# ESP32_WITH_USB_C.net
KiCad netlist of a schematic drawn in Altium Designer
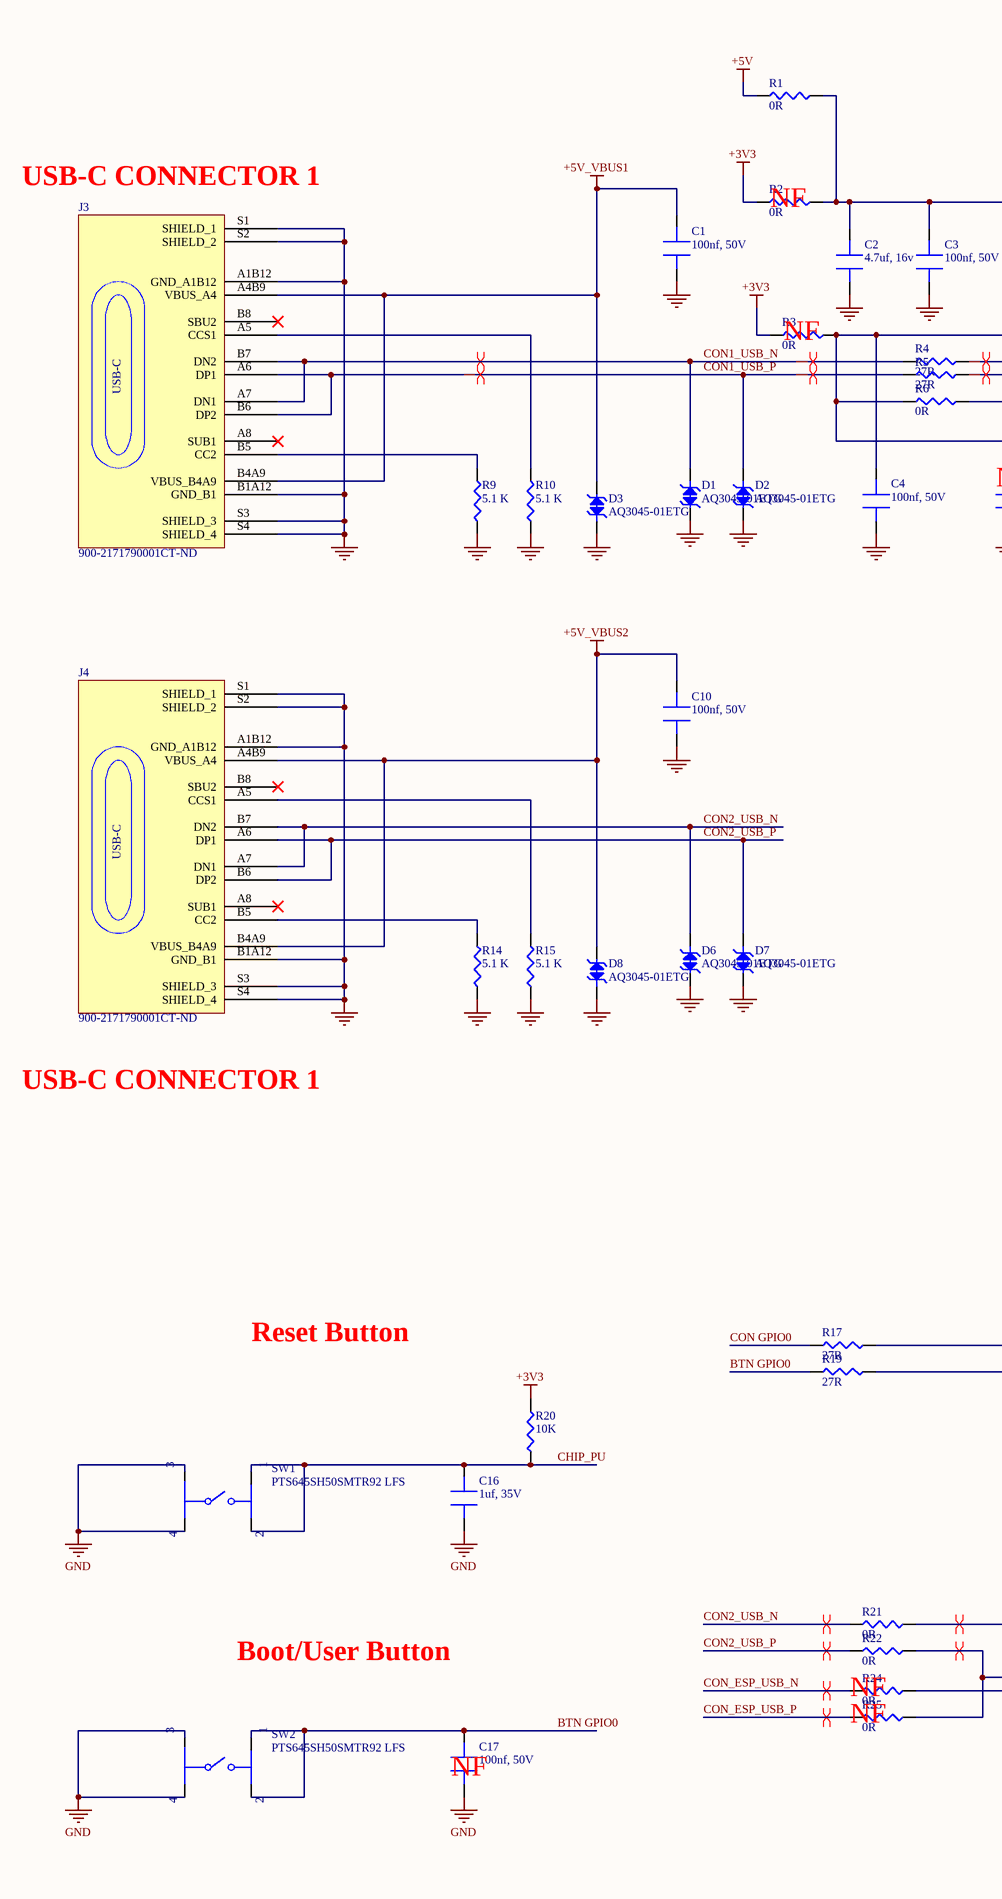
[diagram p0: ESP32 WITH USB C.SchDoc, left]
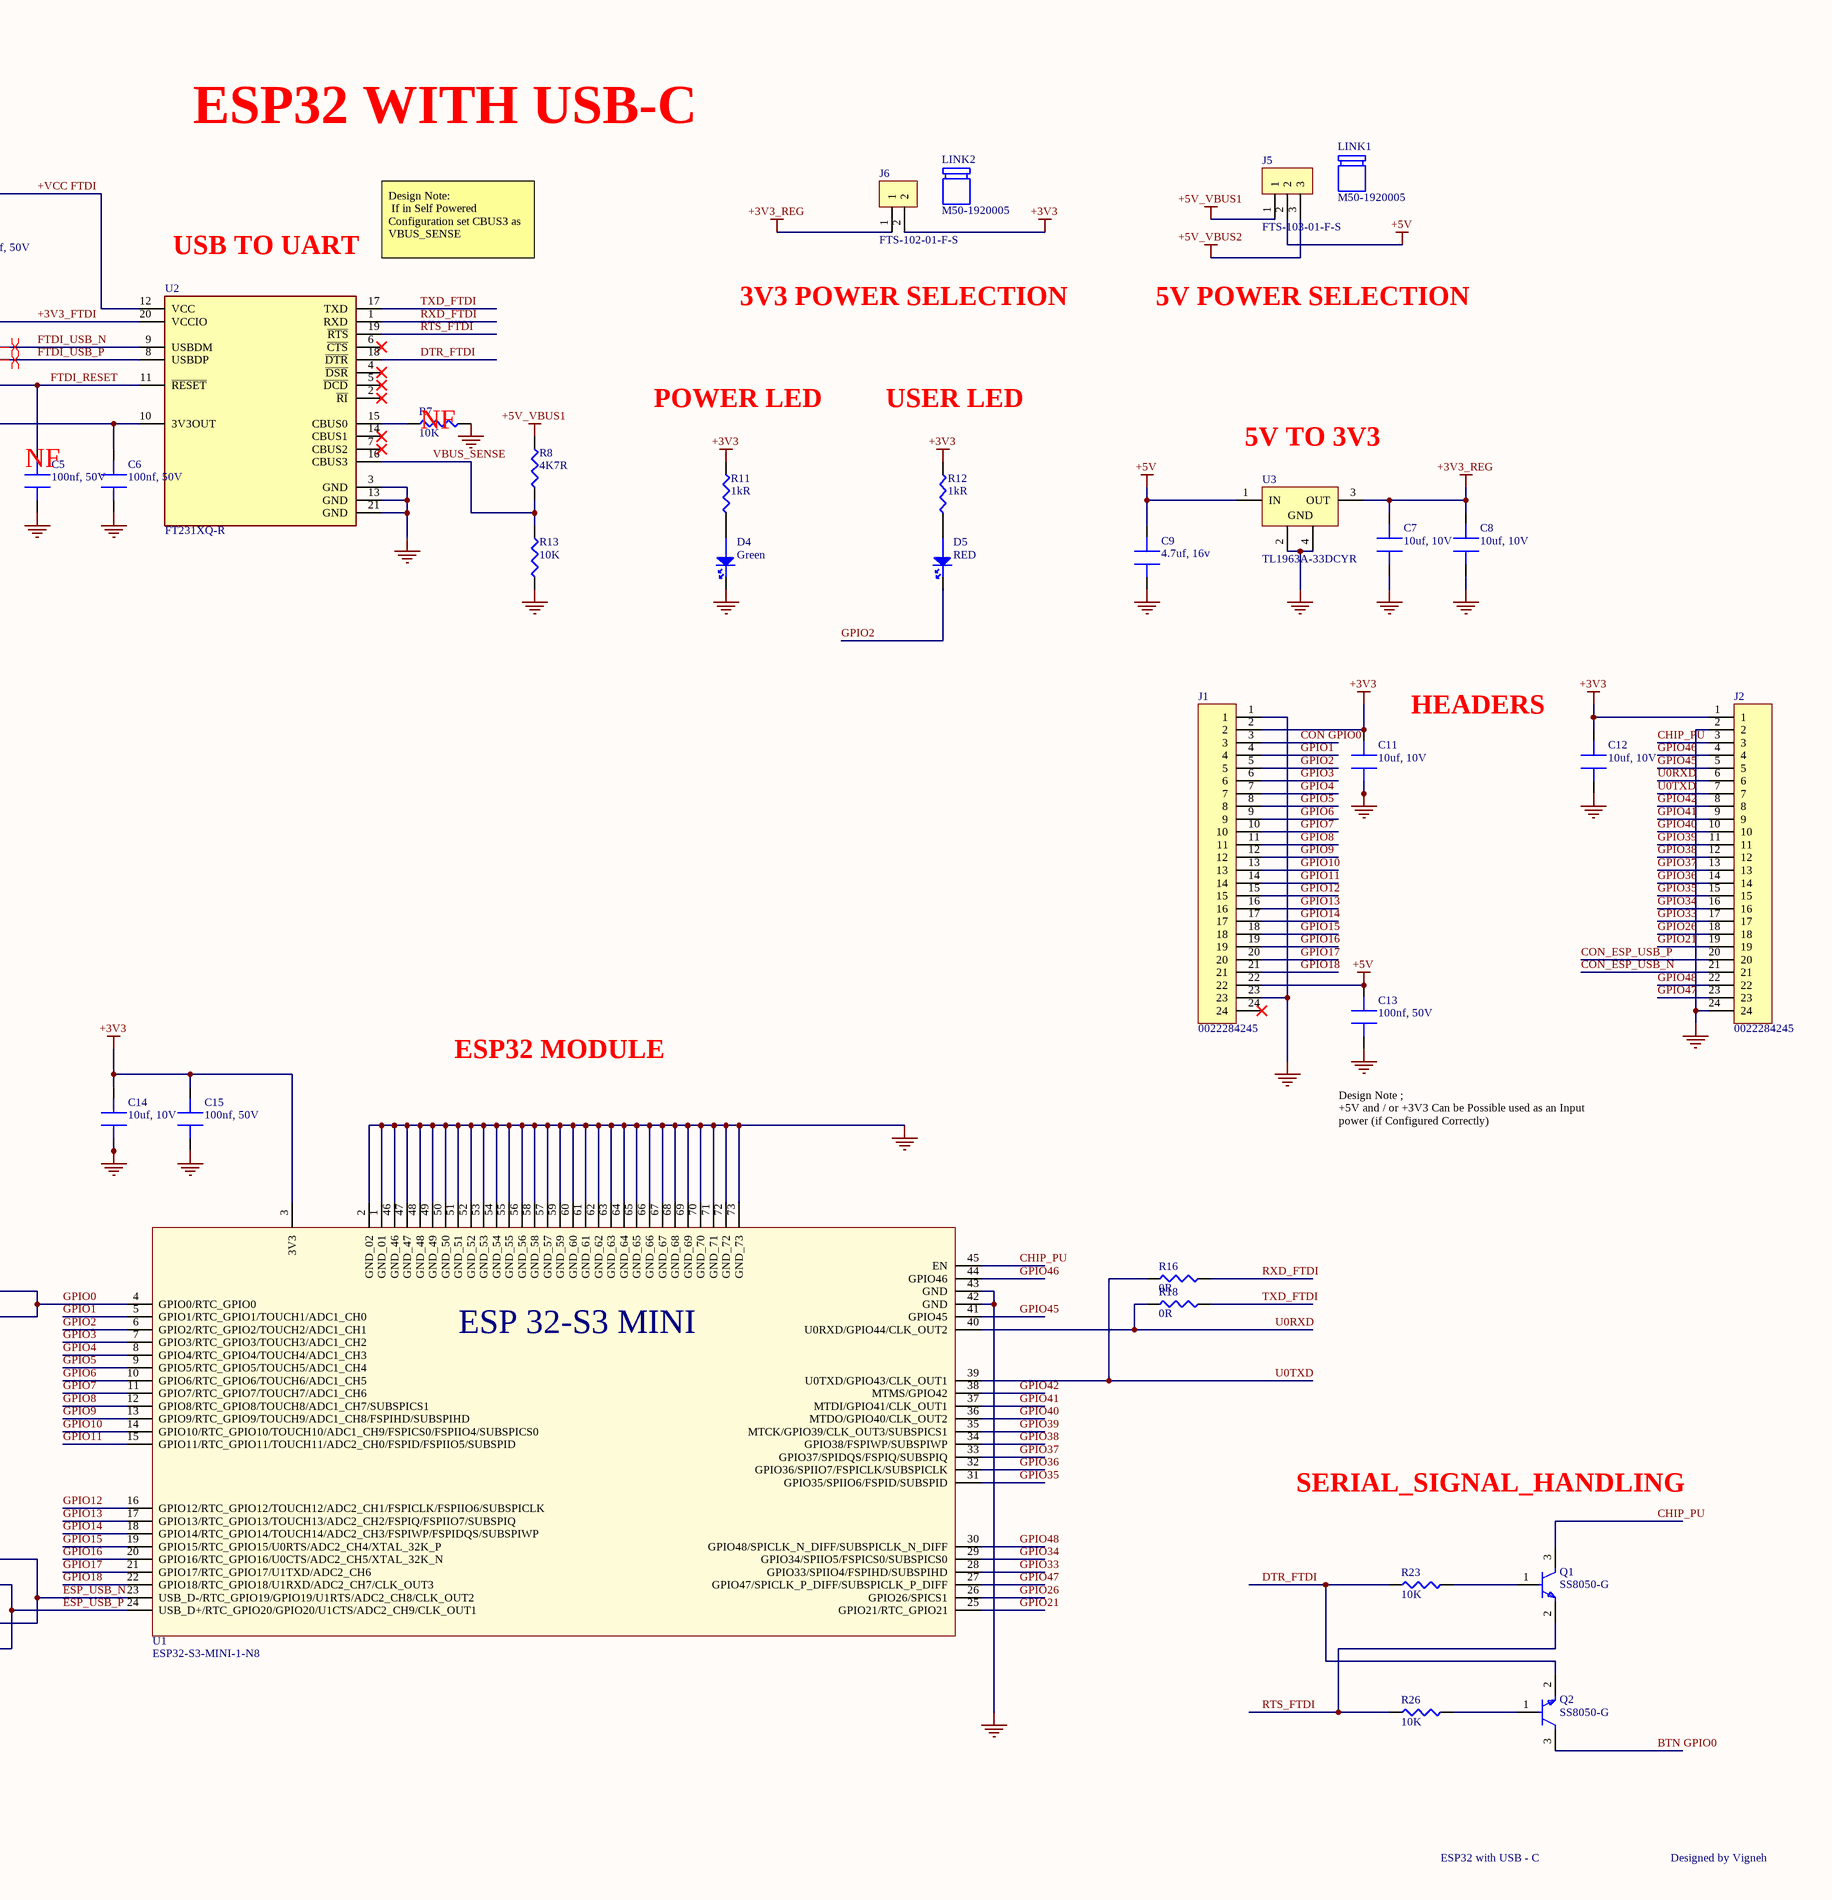
[diagram p1: ESP32 WITH USB C.SchDoc, right]

(export (version "E")
  (design (tool "Eeschema 10.0.6"))
  (components
    (comp (ref "C1")
      (value "100nf, 50V")
      (footprint "CAPC1005X70N")
      (description "CAP CER 0.1UF 50V X7R 0402")
      (fields
        (field (name "MANUFACTURER") "Samsung")
        (field (name "MANUFACTURER PART NUMBER") "CL05B104KB54PNC")
      )
      (libsource (lib "Schlib") (part "CL05B104KB54PNC"))
    )
    (comp (ref "C2")
      (value "4.7uf, 16v")
      (footprint "CAPC1005X70N")
      (description "4.7 µF ±20% 16V Ceramic Capacitor X5R 0402 (1005 Metric)")
      (fields
        (field (name "MANUFACTURER") "Samsung")
        (field (name "MANUFACTURER PART NUMBER") "CL05A475MO5NUNC")
      )
      (libsource (lib "Schlib") (part "CL05A475MO5NUNC"))
    )
    (comp (ref "C3")
      (value "100nf, 50V")
      (footprint "CAPC1005X70N")
      (description "CAP CER 0.1UF 50V X7R 0402")
      (fields
        (field (name "MANUFACTURER") "Samsung")
        (field (name "MANUFACTURER PART NUMBER") "CL05B104KB54PNC")
      )
      (libsource (lib "Schlib") (part "CL05B104KB54PNC"))
    )
    (comp (ref "C4")
      (value "100nf, 50V")
      (footprint "CAPC1005X70N")
      (description "CAP CER 0.1UF 50V X7R 0402")
      (fields
        (field (name "MANUFACTURER") "Samsung")
        (field (name "MANUFACTURER PART NUMBER") "CL05B104KB54PNC")
      )
      (libsource (lib "Schlib") (part "CL05B104KB54PNC"))
    )
    (comp (ref "C5")
      (value "100nf, 50V")
      (footprint "CAPC1005X70N")
      (description "CAP CER 0.1UF 50V X7R 0402")
      (fields
        (field (name "MANUFACTURER") "Samsung")
        (field (name "MANUFACTURER PART NUMBER") "CL05B104KB54PNC")
      )
      (libsource (lib "Schlib") (part "CL05B104KB54PNC"))
    )
    (comp (ref "C6")
      (value "100nf, 50V")
      (footprint "CAPC1005X70N")
      (description "CAP CER 0.1UF 50V X7R 0402")
      (fields
        (field (name "MANUFACTURER") "Samsung")
        (field (name "MANUFACTURER PART NUMBER") "CL05B104KB54PNC")
      )
      (libsource (lib "Schlib") (part "CL05B104KB54PNC"))
    )
    (comp (ref "C7")
      (value "10uf, 10V")
      (footprint "CAPC1005X70N")
      (description "CAP CER 10UF 10V X5R 0402")
      (fields
        (field (name "MANUFACTURER") "Samsung")
        (field (name "MANUFACTURER PART NUMBER") "CL05A106MP8NUB8")
      )
      (libsource (lib "Schlib") (part "CL05A106MP8NUB8"))
    )
    (comp (ref "C8")
      (value "10uf, 10V")
      (footprint "CAPC1005X70N")
      (description "CAP CER 10UF 10V X5R 0402")
      (fields
        (field (name "MANUFACTURER") "Samsung")
        (field (name "MANUFACTURER PART NUMBER") "CL05A106MP8NUB8")
      )
      (libsource (lib "Schlib") (part "CL05A106MP8NUB8"))
    )
    (comp (ref "C9")
      (value "4.7uf, 16v")
      (footprint "CAPC1005X70N")
      (description "4.7 µF ±20% 16V Ceramic Capacitor X5R 0402 (1005 Metric)")
      (fields
        (field (name "MANUFACTURER") "Samsung")
        (field (name "MANUFACTURER PART NUMBER") "CL05A475MO5NUNC")
      )
      (libsource (lib "Schlib") (part "CL05A475MO5NUNC"))
    )
    (comp (ref "C10")
      (value "100nf, 50V")
      (footprint "CAPC1005X70N")
      (description "CAP CER 0.1UF 50V X7R 0402")
      (fields
        (field (name "MANUFACTURER") "Samsung")
        (field (name "MANUFACTURER PART NUMBER") "CL05B104KB54PNC")
      )
      (libsource (lib "Schlib") (part "CL05B104KB54PNC"))
    )
    (comp (ref "C11")
      (value "10uf, 10V")
      (footprint "CAPC1005X70N")
      (description "CAP CER 10UF 10V X5R 0402")
      (fields
        (field (name "MANUFACTURER") "Samsung")
        (field (name "MANUFACTURER PART NUMBER") "CL05A106MP8NUB8")
      )
      (libsource (lib "Schlib") (part "CL05A106MP8NUB8"))
    )
    (comp (ref "C12")
      (value "10uf, 10V")
      (footprint "CAPC1005X70N")
      (description "CAP CER 10UF 10V X5R 0402")
      (fields
        (field (name "MANUFACTURER") "Samsung")
        (field (name "MANUFACTURER PART NUMBER") "CL05A106MP8NUB8")
      )
      (libsource (lib "Schlib") (part "CL05A106MP8NUB8"))
    )
    (comp (ref "C13")
      (value "100nf, 50V")
      (footprint "CAPC1005X70N")
      (description "CAP CER 0.1UF 50V X7R 0402")
      (fields
        (field (name "MANUFACTURER") "Samsung")
        (field (name "MANUFACTURER PART NUMBER") "CL05B104KB54PNC")
      )
      (libsource (lib "Schlib") (part "CL05B104KB54PNC"))
    )
    (comp (ref "C14")
      (value "10uf, 10V")
      (footprint "CAPC1005X70N")
      (description "CAP CER 10UF 10V X5R 0402")
      (fields
        (field (name "MANUFACTURER") "Samsung")
        (field (name "MANUFACTURER PART NUMBER") "CL05A106MP8NUB8")
      )
      (libsource (lib "Schlib") (part "CL05A106MP8NUB8"))
    )
    (comp (ref "C15")
      (value "100nf, 50V")
      (footprint "CAPC1005X70N")
      (description "CAP CER 0.1UF 50V X7R 0402")
      (fields
        (field (name "MANUFACTURER") "Samsung")
        (field (name "MANUFACTURER PART NUMBER") "CL05B104KB54PNC")
      )
      (libsource (lib "Schlib") (part "CL05B104KB54PNC"))
    )
    (comp (ref "C16")
      (value "1uf, 35V")
      (footprint "CAPC1005X70N")
      (description "CAP CER 1UF 35V X5R 0402")
      (fields
        (field (name "MANUFACTURER") "Samsung")
        (field (name "MANUFACTURER PART NUMBER") "CL05A105KL5NRNC")
      )
      (libsource (lib "Schlib") (part "CL05A105KL5NRNC"))
    )
    (comp (ref "C17")
      (value "100nf, 50V")
      (footprint "CAPC1005X70N")
      (description "CAP CER 0.1UF 50V X7R 0402")
      (fields
        (field (name "MANUFACTURER") "Samsung")
        (field (name "MANUFACTURER PART NUMBER") "CL05B104KB54PNC")
      )
      (libsource (lib "Schlib") (part "CL05B104KB54PNC"))
    )
    (comp (ref "D1")
      (value "AQ3045-01ETG")
      (footprint "SOD882")
      (description "TVS DIODE 5.3VWM 12VC SOD882")
      (fields (field (name "MANUFACTURER") "Littelfuse") (field (name "LCSC PART NO") "C3710326"))
      (libsource (lib "Schlib") (part "AQ3045-01ETG"))
    )
    (comp (ref "D2")
      (value "AQ3045-01ETG")
      (footprint "SOD882")
      (description "TVS DIODE 5.3VWM 12VC SOD882")
      (fields (field (name "MANUFACTURER") "Littelfuse") (field (name "LCSC PART NO") "C3710326"))
      (libsource (lib "Schlib") (part "AQ3045-01ETG"))
    )
    (comp (ref "D3")
      (value "AQ3045-01ETG")
      (footprint "SOD882")
      (description "TVS DIODE 5.3VWM 12VC SOD882")
      (fields (field (name "MANUFACTURER") "Littelfuse") (field (name "LCSC PART NO") "C3710326"))
      (libsource (lib "Schlib") (part "AQ3045-01ETG"))
    )
    (comp (ref "D4")
      (value "Green")
      (footprint "LED0402G")
      (description "LED YLW-GRN 0402 SMD")
      (fields
        (field (name "MANUFACTURER") "Vishay")
        (field (name "MANUFACTURER PART NUMBER") "VLMG1500-GS08")
      )
      (libsource (lib "Schlib") (part "VLMG1500-GS08"))
    )
    (comp (ref "D5")
      (value "RED")
      (footprint "LED0402R")
      (description "LED RED 0402 SMD")
      (fields
        (field (name "MANUFACTURER") "Vishay")
        (field (name "MANUFACTURER PART NUMBER") "VLMS1500-GS08")
      )
      (libsource (lib "Schlib") (part "VLMS1500-GS08"))
    )
    (comp (ref "D6")
      (value "AQ3045-01ETG")
      (footprint "SOD882")
      (description "TVS DIODE 5.3VWM 12VC SOD882")
      (fields (field (name "MANUFACTURER") "Littelfuse") (field (name "LCSC PART NO") "C3710326"))
      (libsource (lib "Schlib") (part "AQ3045-01ETG"))
    )
    (comp (ref "D7")
      (value "AQ3045-01ETG")
      (footprint "SOD882")
      (description "TVS DIODE 5.3VWM 12VC SOD882")
      (fields (field (name "MANUFACTURER") "Littelfuse") (field (name "LCSC PART NO") "C3710326"))
      (libsource (lib "Schlib") (part "AQ3045-01ETG"))
    )
    (comp (ref "D8")
      (value "AQ3045-01ETG")
      (footprint "SOD882")
      (description "TVS DIODE 5.3VWM 12VC SOD882")
      (fields (field (name "MANUFACTURER") "Littelfuse") (field (name "LCSC PART NO") "C3710326"))
      (libsource (lib "Schlib") (part "AQ3045-01ETG"))
    )
    (comp (ref "J1")
      (value "0022284245")
      (footprint "HDR_1x24_2.5MM")
      (description "CONN HEADER VERT 24POS 2.54MM")
      (fields (field (name "MANUFACTURER") "Molex") (field (name "MANUFACTURER PART NUMBER") "22-28-4245"))
      (libsource (lib "Schlib") (part "0022284245"))
    )
    (comp (ref "J2")
      (value "0022284245")
      (footprint "HDR_1x24_2.5MM")
      (description "CONN HEADER VERT 24POS 2.54MM")
      (fields (field (name "MANUFACTURER") "Molex") (field (name "MANUFACTURER PART NUMBER") "22-28-4245"))
      (libsource (lib "") (part "0022284245_1"))
    )
    (comp (ref "J3")
      (value "900-2171790001CT-ND")
      (footprint "FP-2171790001-MFG")
      (description "CONN RCP USB2.0 TYP C 24P SMD RA")
      (fields (field (name "MANUFACTURER") "Molex") (field (name "MANUFACTURER PART NUMBER") "217179-0001"))
      (libsource (lib "Schlib") (part "2171790001"))
    )
    (comp (ref "J4")
      (value "900-2171790001CT-ND")
      (footprint "FP-2171790001-MFG")
      (description "CONN RCP USB2.0 TYP C 24P SMD RA")
      (fields (field (name "MANUFACTURER") "Molex") (field (name "MANUFACTURER PART NUMBER") "217179-0001"))
      (libsource (lib "Schlib") (part "2171790001"))
    )
    (comp (ref "J5")
      (value "FTS-103-01-F-S")
      (footprint "HDR_1x3_1.27MM")
      (description "CONN HEADER VERT 3POS 1.27MM")
      (fields (field (name "MANUFACTURER") "Samtec") (field (name "LCSC PART NUMBER") "C3333578"))
      (libsource (lib "Schlib") (part "FTS-103-01-F-S"))
    )
    (comp (ref "J6")
      (value "FTS-102-01-F-S")
      (footprint "HDR_1x2_1.27MM")
      (description "CONN HEADER VERT 2POS 1.27MM")
      (fields (field (name "MANUFACTURER") "Samtec") (field (name "LCSC PART NUMBER") "C6045317"))
      (libsource (lib "Schlib") (part "FTS-102-01-F-S"))
    )
    (comp (ref "LINK1")
      (value "M50-1920005")
      (description "CONN SHUNT 1.27MM RED")
      (fields (field (name "MANUFACTURER") "Harwin") (field (name "LCSC PART NUMBER") "C6985646"))
      (libsource (lib "Schlib") (part "M50-1920005"))
    )
    (comp (ref "LINK2")
      (value "M50-1920005")
      (description "CONN SHUNT 1.27MM RED")
      (fields (field (name "MANUFACTURER") "Harwin") (field (name "LCSC PART NUMBER") "C6985646"))
      (libsource (lib "Schlib") (part "M50-1920005"))
    )
    (comp (ref "Q1")
      (value "SS8050-G")
      (footprint "FP-SS8050-G-IPC_B")
      (description "TRANS NPN 25V 1.5A SOT-23-3")
      (fields (field (name "MANUFACTURER") "Comchip") (field (name "LCSC PART NUMBER") "C164886"))
      (libsource (lib "Schlib") (part "SS8050-G"))
    )
    (comp (ref "Q2")
      (value "SS8050-G")
      (footprint "FP-SS8050-G-IPC_B")
      (description "TRANS NPN 25V 1.5A SOT-23-3")
      (fields (field (name "MANUFACTURER") "Comchip") (field (name "LCSC PART NUMBER") "C164886"))
      (libsource (lib "Schlib") (part "SS8050-G"))
    )
    (comp (ref "R1")
      (value "0R")
      (footprint "RESC1005X40N")
      (description "RES 0 OHM JUMPER 1/16W 0402")
      (fields
        (field (name "MANUFACTURER") "Yageo")
        (field (name "MANUFACTURER PART NUMBER") "RC0402JR-070RL")
      )
      (libsource (lib "Schlib") (part "RC0402JR-070RL"))
    )
    (comp (ref "R2")
      (value "0R")
      (footprint "RESC1005X40N")
      (description "RES 0 OHM JUMPER 1/16W 0402")
      (fields
        (field (name "MANUFACTURER") "Yageo")
        (field (name "MANUFACTURER PART NUMBER") "RC0402JR-070RL")
      )
      (libsource (lib "Schlib") (part "RC0402JR-070RL"))
    )
    (comp (ref "R3")
      (value "0R")
      (footprint "RESC1005X40N")
      (description "RES 0 OHM JUMPER 1/16W 0402")
      (fields
        (field (name "MANUFACTURER") "Yageo")
        (field (name "MANUFACTURER PART NUMBER") "RC0402JR-070RL")
      )
      (libsource (lib "Schlib") (part "RC0402JR-070RL"))
    )
    (comp (ref "R4")
      (value "27R")
      (footprint "RESC1005X40N")
      (description "RES 27 OHM 1% 1/16W 0402")
      (fields
        (field (name "MANUFACTURER") "Yageo")
        (field (name "MANUFACTURER PART NUMBER") "RC0402FR-0727RL")
      )
      (libsource (lib "Schlib") (part "RC0402FR-0727RL"))
    )
    (comp (ref "R5")
      (value "27R")
      (footprint "RESC1005X40N")
      (description "RES 27 OHM 1% 1/16W 0402")
      (fields
        (field (name "MANUFACTURER") "Yageo")
        (field (name "MANUFACTURER PART NUMBER") "RC0402FR-0727RL")
      )
      (libsource (lib "Schlib") (part "RC0402FR-0727RL"))
    )
    (comp (ref "R6")
      (value "0R")
      (footprint "RESC1005X40N")
      (description "RES 0 OHM JUMPER 1/16W 0402")
      (fields
        (field (name "MANUFACTURER") "Yageo")
        (field (name "MANUFACTURER PART NUMBER") "RC0402JR-070RL")
      )
      (libsource (lib "Schlib") (part "RC0402JR-070RL"))
    )
    (comp (ref "R7")
      (value "10K")
      (footprint "RESC1005X40N")
      (description "RES SMD 10K OHM 1% 1/16W 0402")
      (fields
        (field (name "MANUFACTURER") "Yageo")
        (field (name "MANUFACTURER PART NUMBER") "AC0402FR-0710KL")
      )
      (libsource (lib "Schlib") (part "AC0402FR-0710KL"))
    )
    (comp (ref "R8")
      (value "4K7R")
      (footprint "RESC1005X40N")
      (description "RES 4.7K OHM 1% 1/16W 0402")
      (fields
        (field (name "MANUFACTURER") "Yageo")
        (field (name "MANUFACTURER PART NUMBER") "RC0402FR-074K7L")
      )
      (libsource (lib "Schlib") (part "RC0402FR-074K7L"))
    )
    (comp (ref "R9")
      (value "5.1 K")
      (footprint "RESC1005X40N")
      (description "RES 5.1K OHM 1% 1/16W 0402")
      (fields
        (field (name "MANUFACTURER") "Yageo")
        (field (name "MANUFACTURER PART NUMBER") "RC0402FR-075K1L")
      )
      (libsource (lib "Schlib") (part "RC0402FR-075K1L"))
    )
    (comp (ref "R10")
      (value "5.1 K")
      (footprint "RESC1005X40N")
      (description "RES 5.1K OHM 1% 1/16W 0402")
      (fields
        (field (name "MANUFACTURER") "Yageo")
        (field (name "MANUFACTURER PART NUMBER") "RC0402FR-075K1L")
      )
      (libsource (lib "Schlib") (part "RC0402FR-075K1L"))
    )
    (comp (ref "R11")
      (value "1kR")
      (footprint "RESC1005X40N")
      (description "RES 1K OHM 1% 1/16W 0402")
      (fields
        (field (name "MANUFACTURER") "Yageo")
        (field (name "MANUFACTURER PART NUMBER") "RC0402FR-071KL")
      )
      (libsource (lib "Schlib") (part "RC0402FR-071KL"))
    )
    (comp (ref "R12")
      (value "1kR")
      (footprint "RESC1005X40N")
      (description "RES 1K OHM 1% 1/16W 0402")
      (fields
        (field (name "MANUFACTURER") "Yageo")
        (field (name "MANUFACTURER PART NUMBER") "RC0402FR-071KL")
      )
      (libsource (lib "Schlib") (part "RC0402FR-071KL"))
    )
    (comp (ref "R13")
      (value "10K")
      (footprint "RESC1005X40N")
      (description "RES SMD 10K OHM 1% 1/16W 0402")
      (fields
        (field (name "MANUFACTURER") "Yageo")
        (field (name "MANUFACTURER PART NUMBER") "AC0402FR-0710KL")
      )
      (libsource (lib "Schlib") (part "AC0402FR-0710KL"))
    )
    (comp (ref "R14")
      (value "5.1 K")
      (footprint "RESC1005X40N")
      (description "RES 5.1K OHM 1% 1/16W 0402")
      (fields
        (field (name "MANUFACTURER") "Yageo")
        (field (name "MANUFACTURER PART NUMBER") "RC0402FR-075K1L")
      )
      (libsource (lib "Schlib") (part "RC0402FR-075K1L"))
    )
    (comp (ref "R15")
      (value "5.1 K")
      (footprint "RESC1005X40N")
      (description "RES 5.1K OHM 1% 1/16W 0402")
      (fields
        (field (name "MANUFACTURER") "Yageo")
        (field (name "MANUFACTURER PART NUMBER") "RC0402FR-075K1L")
      )
      (libsource (lib "Schlib") (part "RC0402FR-075K1L"))
    )
    (comp (ref "R16")
      (value "0R")
      (footprint "RESC1005X40N")
      (description "RES 0 OHM JUMPER 1/16W 0402")
      (fields
        (field (name "MANUFACTURER") "Yageo")
        (field (name "MANUFACTURER PART NUMBER") "RC0402JR-070RL")
      )
      (libsource (lib "Schlib") (part "RC0402JR-070RL"))
    )
    (comp (ref "R17")
      (value "27R")
      (footprint "RESC1005X40N")
      (description "RES 27 OHM 1% 1/16W 0402")
      (fields
        (field (name "MANUFACTURER") "Yageo")
        (field (name "MANUFACTURER PART NUMBER") "RC0402FR-0727RL")
      )
      (libsource (lib "Schlib") (part "RC0402FR-0727RL"))
    )
    (comp (ref "R18")
      (value "0R")
      (footprint "RESC1005X40N")
      (description "RES 0 OHM JUMPER 1/16W 0402")
      (fields
        (field (name "MANUFACTURER") "Yageo")
        (field (name "MANUFACTURER PART NUMBER") "RC0402JR-070RL")
      )
      (libsource (lib "Schlib") (part "RC0402JR-070RL"))
    )
    (comp (ref "R19")
      (value "27R")
      (footprint "RESC1005X40N")
      (description "RES 27 OHM 1% 1/16W 0402")
      (fields
        (field (name "MANUFACTURER") "Yageo")
        (field (name "MANUFACTURER PART NUMBER") "RC0402FR-0727RL")
      )
      (libsource (lib "Schlib") (part "RC0402FR-0727RL"))
    )
    (comp (ref "R20")
      (value "10K")
      (footprint "RESC1005X40N")
      (description "RES SMD 10K OHM 1% 1/16W 0402")
      (fields
        (field (name "MANUFACTURER") "Yageo")
        (field (name "MANUFACTURER PART NUMBER") "AC0402FR-0710KL")
      )
      (libsource (lib "Schlib") (part "AC0402FR-0710KL"))
    )
    (comp (ref "R21")
      (value "0R")
      (footprint "RESC1005X40N")
      (description "RES 0 OHM JUMPER 1/16W 0402")
      (fields
        (field (name "MANUFACTURER") "Yageo")
        (field (name "MANUFACTURER PART NUMBER") "RC0402JR-070RL")
      )
      (libsource (lib "Schlib") (part "RC0402JR-070RL"))
    )
    (comp (ref "R22")
      (value "0R")
      (footprint "RESC1005X40N")
      (description "RES 0 OHM JUMPER 1/16W 0402")
      (fields
        (field (name "MANUFACTURER") "Yageo")
        (field (name "MANUFACTURER PART NUMBER") "RC0402JR-070RL")
      )
      (libsource (lib "Schlib") (part "RC0402JR-070RL"))
    )
    (comp (ref "R23")
      (value "10K")
      (footprint "RESC1005X40N")
      (description "RES SMD 10K OHM 1% 1/16W 0402")
      (fields
        (field (name "MANUFACTURER") "Yageo")
        (field (name "MANUFACTURER PART NUMBER") "AC0402FR-0710KL")
      )
      (libsource (lib "Schlib") (part "AC0402FR-0710KL"))
    )
    (comp (ref "R24")
      (value "0R")
      (footprint "RESC1005X40N")
      (description "RES 0 OHM JUMPER 1/16W 0402")
      (fields
        (field (name "MANUFACTURER") "Yageo")
        (field (name "MANUFACTURER PART NUMBER") "RC0402JR-070RL")
      )
      (libsource (lib "Schlib") (part "RC0402JR-070RL"))
    )
    (comp (ref "R25")
      (value "0R")
      (footprint "RESC1005X40N")
      (description "RES 0 OHM JUMPER 1/16W 0402")
      (fields
        (field (name "MANUFACTURER") "Yageo")
        (field (name "MANUFACTURER PART NUMBER") "RC0402JR-070RL")
      )
      (libsource (lib "Schlib") (part "RC0402JR-070RL"))
    )
    (comp (ref "R26")
      (value "10K")
      (footprint "RESC1005X40N")
      (description "RES SMD 10K OHM 1% 1/16W 0402")
      (fields
        (field (name "MANUFACTURER") "Yageo")
        (field (name "MANUFACTURER PART NUMBER") "AC0402FR-0710KL")
      )
      (libsource (lib "Schlib") (part "AC0402FR-0710KL"))
    )
    (comp (ref "SW1")
      (value "PTS645SH50SMTR92 LFS")
      (footprint "FP-PTS645SH50SMTR92LFS-MFG")
      (description "SWITCH TACTILE SPST-NO 0.05A 12V")
      (fields
        (field (name "MANUFACTURER") "ITT C&K")
        (field (name "MANUFACTURER PART NUMBER") "PTS645SH50SMTR92LFS")
      )
      (libsource (lib "Schlib") (part "PTS645SH50SMTR92LFS"))
    )
    (comp (ref "SW2")
      (value "PTS645SH50SMTR92 LFS")
      (footprint "FP-PTS645SH50SMTR92LFS-MFG")
      (description "SWITCH TACTILE SPST-NO 0.05A 12V")
      (fields
        (field (name "MANUFACTURER") "ITT C&K")
        (field (name "MANUFACTURER PART NUMBER") "PTS645SH50SMTR92LFS")
      )
      (libsource (lib "Schlib") (part "PTS645SH50SMTR92LFS"))
    )
    (comp (ref "U1")
      (value "ESP32-S3-MINI-1-N8")
      (footprint "XCVR_ESP32-S3-MINI-1-N8")
      (description "SMD module, ESP32-S3FN8, 8 MB SPI flash, PCB antenna")
      (fields (field (name "MANUFACTURER") "Espressif Systems") (field (name "LCSC PART NUMBER") "C2913206"))
      (libsource (lib "Schlib") (part "ESP32-S3-MINI-1-N8"))
    )
    (comp (ref "U2")
      (value "FT231XQ-R")
      (footprint "FP-QFN-20-IPC_B")
      (description "IC USB SERIAL FULL UART 20QFN")
      (fields (field (name "MANUFACTURER") "FTDI") (field (name "LCSC PART NUMBER") "C132159"))
      (libsource (lib "Schlib") (part "FT231XQ-R"))
    )
    (comp (ref "U3")
      (value "TL1963A-33DCYR")
      (footprint "DCY0004A_N")
      (description "IC REG LIN 3.3V 1.5A SOT-223-4")
      (fields (field (name "MANUFACTURER") "Texas Instruments") (field (name "LCSC PART NUMBER") "C181262"))
      (libsource (lib "Schlib") (part "TL1963A-33DCYR"))
    )
  )
  (nets
    (net (code "1") (name "+3V3") (class "Default")
      (node (ref "C11") (pin "2") (pinfunction "2_2") (pintype "passive"))
      (node (ref "C12") (pin "2") (pinfunction "2_2") (pintype "passive"))
      (node (ref "C14") (pin "2") (pinfunction "2_2") (pintype "passive"))
      (node (ref "C15") (pin "2") (pinfunction "2_2") (pintype "passive"))
      (node (ref "J1") (pin "2") (pinfunction "2_2") (pintype "passive"))
      (node (ref "J2") (pin "1") (pinfunction "1_1") (pintype "passive"))
      (node (ref "J6") (pin "2") (pinfunction "2_2") (pintype "passive"))
      (node (ref "R11") (pin "2") (pinfunction "2_2") (pintype "passive"))
      (node (ref "R12") (pin "2") (pinfunction "2_2") (pintype "passive"))
      (node (ref "R2") (pin "1") (pinfunction "1_1") (pintype "passive"))
      (node (ref "R20") (pin "2") (pinfunction "2_2") (pintype "passive"))
      (node (ref "R3") (pin "1") (pinfunction "1_1") (pintype "passive"))
      (node (ref "U1") (pin "3") (pinfunction "3V3_3") (pintype "passive"))
    )
    (net (code "2") (name "+3V3_REG") (class "Default")
      (node (ref "C7") (pin "2") (pinfunction "2_2") (pintype "passive"))
      (node (ref "C8") (pin "2") (pinfunction "2_2") (pintype "passive"))
      (node (ref "J6") (pin "1") (pinfunction "1_1") (pintype "passive"))
      (node (ref "U3") (pin "3") (pinfunction "OUT_3") (pintype "power_in"))
    )
    (net (code "3") (name "+5V") (class "Default")
      (node (ref "C13") (pin "2") (pinfunction "2_2") (pintype "passive"))
      (node (ref "C9") (pin "2") (pinfunction "2_2") (pintype "passive"))
      (node (ref "J1") (pin "22") (pinfunction "22_22") (pintype "passive"))
      (node (ref "J5") (pin "2") (pinfunction "2_2") (pintype "passive"))
      (node (ref "R1") (pin "1") (pinfunction "1_1") (pintype "passive"))
      (node (ref "U3") (pin "1") (pinfunction "IN_1") (pintype "power_in"))
    )
    (net (code "4") (name "+5V_VBUS1") (class "Default")
      (node (ref "C1") (pin "2") (pinfunction "2_2") (pintype "passive"))
      (node (ref "D3") (pin "1") (pinfunction "1_1") (pintype "passive"))
      (node (ref "J3") (pin "A4B9") (pinfunction "VBUS_A4_A4B9") (pintype "passive"))
      (node (ref "J3") (pin "B4A9") (pinfunction "VBUS_B4A9_B4A9") (pintype "passive"))
      (node (ref "J5") (pin "1") (pinfunction "1_1") (pintype "passive"))
      (node (ref "R8") (pin "2") (pinfunction "2_2") (pintype "passive"))
    )
    (net (code "5") (name "+5V_VBUS2") (class "Default")
      (node (ref "C10") (pin "2") (pinfunction "2_2") (pintype "passive"))
      (node (ref "D8") (pin "1") (pinfunction "1_1") (pintype "passive"))
      (node (ref "J4") (pin "A4B9") (pinfunction "VBUS_A4_A4B9") (pintype "passive"))
      (node (ref "J4") (pin "B4A9") (pinfunction "VBUS_B4A9_B4A9") (pintype "passive"))
      (node (ref "J5") (pin "3") (pinfunction "3_3") (pintype "passive"))
    )
    (net (code "6") (name "/+3V3_FTDI") (class "Default")
      (node (ref "C4") (pin "2") (pinfunction "2_2") (pintype "passive"))
      (node (ref "C6") (pin "2") (pinfunction "2_2") (pintype "passive"))
      (node (ref "R3") (pin "2") (pinfunction "2_2") (pintype "passive"))
      (node (ref "R6") (pin "1") (pinfunction "1_1") (pintype "passive"))
      (node (ref "U2") (pin "10") (pinfunction "3V3OUT_10") (pintype "passive"))
      (node (ref "U2") (pin "20") (pinfunction "VCCIO_20") (pintype "passive"))
    )
    (net (code "7") (name "/+VCC FTDI") (class "Default")
      (node (ref "C2") (pin "2") (pinfunction "2_2") (pintype "passive"))
      (node (ref "C3") (pin "2") (pinfunction "2_2") (pintype "passive"))
      (node (ref "R1") (pin "2") (pinfunction "2_2") (pintype "passive"))
      (node (ref "R2") (pin "2") (pinfunction "2_2") (pintype "passive"))
      (node (ref "U2") (pin "12") (pinfunction "VCC_12") (pintype "passive"))
    )
    (net (code "8") (name "/BTN GPIO0") (class "Default")
      (node (ref "C17") (pin "2") (pinfunction "2_2") (pintype "passive"))
      (node (ref "Q2") (pin "3") (pinfunction "C_3") (pintype "passive"))
      (node (ref "R19") (pin "2") (pinfunction "2_2") (pintype "passive"))
      (node (ref "SW2") (pin "1") (pinfunction "1_1") (pintype "passive"))
      (node (ref "SW2") (pin "2") (pinfunction "2_2") (pintype "passive"))
    )
    (net (code "9") (name "/CHIP_PU") (class "Default")
      (node (ref "C16") (pin "2") (pinfunction "2_2") (pintype "passive"))
      (node (ref "J2") (pin "3") (pinfunction "3_3") (pintype "passive"))
      (node (ref "Q1") (pin "3") (pinfunction "C_3") (pintype "passive"))
      (node (ref "R20") (pin "1") (pinfunction "1_1") (pintype "passive"))
      (node (ref "SW1") (pin "1") (pinfunction "1_1") (pintype "passive"))
      (node (ref "SW1") (pin "2") (pinfunction "2_2") (pintype "passive"))
      (node (ref "U1") (pin "45") (pinfunction "EN_45") (pintype "passive"))
    )
    (net (code "10") (name "/CON GPIO0") (class "Default")
      (node (ref "J1") (pin "3") (pinfunction "3_3") (pintype "passive"))
      (node (ref "R17") (pin "2") (pinfunction "2_2") (pintype "passive"))
    )
    (net (code "11") (name "/CON1_USB_N") (class "Default")
      (node (ref "D1") (pin "2") (pinfunction "2_2") (pintype "passive"))
      (node (ref "J3") (pin "A7") (pinfunction "DN1_A7") (pintype "passive"))
      (node (ref "J3") (pin "B7") (pinfunction "DN2_B7") (pintype "passive"))
      (node (ref "R4") (pin "2") (pinfunction "2_2") (pintype "passive"))
    )
    (net (code "12") (name "/CON1_USB_P") (class "Default")
      (node (ref "D2") (pin "2") (pinfunction "2_2") (pintype "passive"))
      (node (ref "J3") (pin "A6") (pinfunction "DP1_A6") (pintype "passive"))
      (node (ref "J3") (pin "B6") (pinfunction "DP2_B6") (pintype "passive"))
      (node (ref "R5") (pin "2") (pinfunction "2_2") (pintype "passive"))
    )
    (net (code "13") (name "/CON2_USB_N") (class "Default")
      (node (ref "D6") (pin "2") (pinfunction "2_2") (pintype "passive"))
      (node (ref "J4") (pin "A7") (pinfunction "DN1_A7") (pintype "passive"))
      (node (ref "J4") (pin "B7") (pinfunction "DN2_B7") (pintype "passive"))
      (node (ref "R21") (pin "1") (pinfunction "1_1") (pintype "passive"))
    )
    (net (code "14") (name "/CON2_USB_P") (class "Default")
      (node (ref "D7") (pin "2") (pinfunction "2_2") (pintype "passive"))
      (node (ref "J4") (pin "A6") (pinfunction "DP1_A6") (pintype "passive"))
      (node (ref "J4") (pin "B6") (pinfunction "DP2_B6") (pintype "passive"))
      (node (ref "R22") (pin "1") (pinfunction "1_1") (pintype "passive"))
    )
    (net (code "15") (name "/CON_ESP_USB_N") (class "Default")
      (node (ref "J2") (pin "21") (pinfunction "21_21") (pintype "passive"))
      (node (ref "R24") (pin "1") (pinfunction "1_1") (pintype "passive"))
    )
    (net (code "16") (name "/CON_ESP_USB_P") (class "Default")
      (node (ref "J2") (pin "20") (pinfunction "20_20") (pintype "passive"))
      (node (ref "R25") (pin "1") (pinfunction "1_1") (pintype "passive"))
    )
    (net (code "17") (name "/DTR_FTDI") (class "Default")
      (node (ref "Q2") (pin "2") (pinfunction "E_2") (pintype "passive"))
      (node (ref "R23") (pin "2") (pinfunction "2_2") (pintype "passive"))
      (node (ref "U2") (pin "18") (pinfunction "~{DTR}_18") (pintype "passive"))
    )
    (net (code "18") (name "/ESP_USB_N") (class "Default")
      (node (ref "R21") (pin "2") (pinfunction "2_2") (pintype "passive"))
      (node (ref "R24") (pin "2") (pinfunction "2_2") (pintype "passive"))
      (node (ref "U1") (pin "23") (pinfunction "USB_D-/RTC_GPIO19/GPIO19/U1RTS/ADC2_CH8/CLK_OUT2_23") (pintype "passive"))
    )
    (net (code "19") (name "/ESP_USB_P") (class "Default")
      (node (ref "R22") (pin "2") (pinfunction "2_2") (pintype "passive"))
      (node (ref "R25") (pin "2") (pinfunction "2_2") (pintype "passive"))
      (node (ref "U1") (pin "24") (pinfunction "USB_D+/RTC_GPIO20/GPIO20/U1CTS/ADC2_CH9/CLK_OUT1_24") (pintype "passive"))
    )
    (net (code "20") (name "/FTDI_RESET") (class "Default")
      (node (ref "C5") (pin "2") (pinfunction "2_2") (pintype "passive"))
      (node (ref "R6") (pin "2") (pinfunction "2_2") (pintype "passive"))
      (node (ref "U2") (pin "11") (pinfunction "~{RESET}_11") (pintype "passive"))
    )
    (net (code "21") (name "/FTDI_USB_N") (class "Default")
      (node (ref "R4") (pin "1") (pinfunction "1_1") (pintype "passive"))
      (node (ref "U2") (pin "9") (pinfunction "USBDM_9") (pintype "passive"))
    )
    (net (code "22") (name "/FTDI_USB_P") (class "Default")
      (node (ref "R5") (pin "1") (pinfunction "1_1") (pintype "passive"))
      (node (ref "U2") (pin "8") (pinfunction "USBDP_8") (pintype "passive"))
    )
    (net (code "23") (name "/GPIO0") (class "Default")
      (node (ref "R17") (pin "1") (pinfunction "1_1") (pintype "passive"))
      (node (ref "R19") (pin "1") (pinfunction "1_1") (pintype "passive"))
      (node (ref "U1") (pin "4") (pinfunction "GPIO0/RTC_GPIO0_4") (pintype "passive"))
    )
    (net (code "24") (name "/GPIO1") (class "Default")
      (node (ref "J1") (pin "4") (pinfunction "4_4") (pintype "passive"))
      (node (ref "U1") (pin "5") (pinfunction "GPIO1/RTC_GPIO1/TOUCH1/ADC1_CH0_5") (pintype "passive"))
    )
    (net (code "25") (name "/GPIO2") (class "Default")
      (node (ref "D5") (pin "1") (pinfunction "1_1") (pintype "passive"))
      (node (ref "J1") (pin "5") (pinfunction "5_5") (pintype "passive"))
      (node (ref "U1") (pin "6") (pinfunction "GPIO2/RTC_GPIO2/TOUCH2/ADC1_CH1_6") (pintype "passive"))
    )
    (net (code "26") (name "/GPIO3") (class "Default")
      (node (ref "J1") (pin "6") (pinfunction "6_6") (pintype "passive"))
      (node (ref "U1") (pin "7") (pinfunction "GPIO3/RTC_GPIO3/TOUCH3/ADC1_CH2_7") (pintype "passive"))
    )
    (net (code "27") (name "/GPIO4") (class "Default")
      (node (ref "J1") (pin "7") (pinfunction "7_7") (pintype "passive"))
      (node (ref "U1") (pin "8") (pinfunction "GPIO4/RTC_GPIO4/TOUCH4/ADC1_CH3_8") (pintype "passive"))
    )
    (net (code "28") (name "/GPIO5") (class "Default")
      (node (ref "J1") (pin "8") (pinfunction "8_8") (pintype "passive"))
      (node (ref "U1") (pin "9") (pinfunction "GPIO5/RTC_GPIO5/TOUCH5/ADC1_CH4_9") (pintype "passive"))
    )
    (net (code "29") (name "/GPIO6") (class "Default")
      (node (ref "J1") (pin "9") (pinfunction "9_9") (pintype "passive"))
      (node (ref "U1") (pin "10") (pinfunction "GPIO6/RTC_GPIO6/TOUCH6/ADC1_CH5_10") (pintype "passive"))
    )
    (net (code "30") (name "/GPIO7") (class "Default")
      (node (ref "J1") (pin "10") (pinfunction "10_10") (pintype "passive"))
      (node (ref "U1") (pin "11") (pinfunction "GPIO7/RTC_GPIO7/TOUCH7/ADC1_CH6_11") (pintype "passive"))
    )
    (net (code "31") (name "/GPIO8") (class "Default")
      (node (ref "J1") (pin "11") (pinfunction "11_11") (pintype "passive"))
      (node (ref "U1") (pin "12") (pinfunction "GPIO8/RTC_GPIO8/TOUCH8/ADC1_CH7/SUBSPICS1_12") (pintype "passive"))
    )
    (net (code "32") (name "/GPIO9") (class "Default")
      (node (ref "J1") (pin "12") (pinfunction "12_12") (pintype "passive"))
      (node (ref "U1") (pin "13") (pinfunction "GPIO9/RTC_GPIO9/TOUCH9/ADC1_CH8/FSPIHD/SUBSPIHD_13") (pintype "passive"))
    )
    (net (code "33") (name "/GPIO10") (class "Default")
      (node (ref "J1") (pin "13") (pinfunction "13_13") (pintype "passive"))
      (node (ref "U1") (pin "14") (pinfunction "GPIO10/RTC_GPIO10/TOUCH10/ADC1_CH9/FSPICS0/FSPIIO4/SUBSPICS0_14") (pintype "passive"))
    )
    (net (code "34") (name "/GPIO11") (class "Default")
      (node (ref "J1") (pin "14") (pinfunction "14_14") (pintype "passive"))
      (node (ref "U1") (pin "15") (pinfunction "GPIO11/RTC_GPIO11/TOUCH11/ADC2_CH0/FSPID/FSPIIO5/SUBSPID_15") (pintype "passive"))
    )
    (net (code "35") (name "/GPIO12") (class "Default")
      (node (ref "J1") (pin "15") (pinfunction "15_15") (pintype "passive"))
      (node (ref "U1") (pin "16") (pinfunction "GPIO12/RTC_GPIO12/TOUCH12/ADC2_CH1/FSPICLK/FSPIIO6/SUBSPICLK_16") (pintype "passive"))
    )
    (net (code "36") (name "/GPIO13") (class "Default")
      (node (ref "J1") (pin "16") (pinfunction "16_16") (pintype "passive"))
      (node (ref "U1") (pin "17") (pinfunction "GPIO13/RTC_GPIO13/TOUCH13/ADC2_CH2/FSPIQ/FSPIIO7/SUBSPIQ_17") (pintype "passive"))
    )
    (net (code "37") (name "/GPIO14") (class "Default")
      (node (ref "J1") (pin "17") (pinfunction "17_17") (pintype "passive"))
      (node (ref "U1") (pin "18") (pinfunction "GPIO14/RTC_GPIO14/TOUCH14/ADC2_CH3/FSPIWP/FSPIDQS/SUBSPIWP_18") (pintype "passive"))
    )
    (net (code "38") (name "/GPIO15") (class "Default")
      (node (ref "J1") (pin "18") (pinfunction "18_18") (pintype "passive"))
      (node (ref "U1") (pin "19") (pinfunction "GPIO15/RTC_GPIO15/U0RTS/ADC2_CH4/XTAL_32K_P_19") (pintype "passive"))
    )
    (net (code "39") (name "/GPIO16") (class "Default")
      (node (ref "J1") (pin "19") (pinfunction "19_19") (pintype "passive"))
      (node (ref "U1") (pin "20") (pinfunction "GPIO16/RTC_GPIO16/U0CTS/ADC2_CH5/XTAL_32K_N_20") (pintype "passive"))
    )
    (net (code "40") (name "/GPIO17") (class "Default")
      (node (ref "J1") (pin "20") (pinfunction "20_20") (pintype "passive"))
      (node (ref "U1") (pin "21") (pinfunction "GPIO17/RTC_GPIO17/U1TXD/ADC2_CH6_21") (pintype "passive"))
    )
    (net (code "41") (name "/GPIO18") (class "Default")
      (node (ref "J1") (pin "21") (pinfunction "21_21") (pintype "passive"))
      (node (ref "U1") (pin "22") (pinfunction "GPIO18/RTC_GPIO18/U1RXD/ADC2_CH7/CLK_OUT3_22") (pintype "passive"))
    )
    (net (code "42") (name "/GPIO21") (class "Default")
      (node (ref "J2") (pin "19") (pinfunction "19_19") (pintype "passive"))
      (node (ref "U1") (pin "25") (pinfunction "GPIO21/RTC_GPIO21_25") (pintype "passive"))
    )
    (net (code "43") (name "/GPIO26") (class "Default")
      (node (ref "J2") (pin "18") (pinfunction "18_18") (pintype "passive"))
      (node (ref "U1") (pin "26") (pinfunction "GPIO26/SPICS1_26") (pintype "passive"))
    )
    (net (code "44") (name "/GPIO33") (class "Default")
      (node (ref "J2") (pin "17") (pinfunction "17_17") (pintype "passive"))
      (node (ref "U1") (pin "28") (pinfunction "GPIO33/SPIIO4/FSPIHD/SUBSPIHD_28") (pintype "passive"))
    )
    (net (code "45") (name "/GPIO34") (class "Default")
      (node (ref "J2") (pin "16") (pinfunction "16_16") (pintype "passive"))
      (node (ref "U1") (pin "29") (pinfunction "GPIO34/SPIIO5/FSPICS0/SUBSPICS0_29") (pintype "passive"))
    )
    (net (code "46") (name "/GPIO35") (class "Default")
      (node (ref "J2") (pin "15") (pinfunction "15_15") (pintype "passive"))
      (node (ref "U1") (pin "31") (pinfunction "GPIO35/SPIIO6/FSPID/SUBSPID_31") (pintype "passive"))
    )
    (net (code "47") (name "/GPIO36") (class "Default")
      (node (ref "J2") (pin "14") (pinfunction "14_14") (pintype "passive"))
      (node (ref "U1") (pin "32") (pinfunction "GPIO36/SPIIO7/FSPICLK/SUBSPICLK_32") (pintype "passive"))
    )
    (net (code "48") (name "/GPIO37") (class "Default")
      (node (ref "J2") (pin "13") (pinfunction "13_13") (pintype "passive"))
      (node (ref "U1") (pin "33") (pinfunction "GPIO37/SPIDQS/FSPIQ/SUBSPIQ_33") (pintype "passive"))
    )
    (net (code "49") (name "/GPIO38") (class "Default")
      (node (ref "J2") (pin "12") (pinfunction "12_12") (pintype "passive"))
      (node (ref "U1") (pin "34") (pinfunction "GPIO38/FSPIWP/SUBSPIWP_34") (pintype "passive"))
    )
    (net (code "50") (name "/GPIO39") (class "Default")
      (node (ref "J2") (pin "11") (pinfunction "11_11") (pintype "passive"))
      (node (ref "U1") (pin "35") (pinfunction "MTCK/GPIO39/CLK_OUT3/SUBSPICS1_35") (pintype "passive"))
    )
    (net (code "51") (name "/GPIO40") (class "Default")
      (node (ref "J2") (pin "10") (pinfunction "10_10") (pintype "passive"))
      (node (ref "U1") (pin "36") (pinfunction "MTDO/GPIO40/CLK_OUT2_36") (pintype "passive"))
    )
    (net (code "52") (name "/GPIO41") (class "Default")
      (node (ref "J2") (pin "9") (pinfunction "9_9") (pintype "passive"))
      (node (ref "U1") (pin "37") (pinfunction "MTDI/GPIO41/CLK_OUT1_37") (pintype "passive"))
    )
    (net (code "53") (name "/GPIO42") (class "Default")
      (node (ref "J2") (pin "8") (pinfunction "8_8") (pintype "passive"))
      (node (ref "U1") (pin "38") (pinfunction "MTMS/GPIO42_38") (pintype "passive"))
    )
    (net (code "54") (name "/GPIO45") (class "Default")
      (node (ref "J2") (pin "5") (pinfunction "5_5") (pintype "passive"))
      (node (ref "U1") (pin "41") (pinfunction "GPIO45_41") (pintype "passive"))
    )
    (net (code "55") (name "/GPIO46") (class "Default")
      (node (ref "J2") (pin "4") (pinfunction "4_4") (pintype "passive"))
      (node (ref "U1") (pin "44") (pinfunction "GPIO46_44") (pintype "passive"))
    )
    (net (code "56") (name "/GPIO47") (class "Default")
      (node (ref "J2") (pin "23") (pinfunction "23_23") (pintype "passive"))
      (node (ref "U1") (pin "27") (pinfunction "GPIO47/SPICLK_P_DIFF/SUBSPICLK_P_DIFF_27") (pintype "passive"))
    )
    (net (code "57") (name "/GPIO48") (class "Default")
      (node (ref "J2") (pin "22") (pinfunction "22_22") (pintype "passive"))
      (node (ref "U1") (pin "30") (pinfunction "GPIO48/SPICLK_N_DIFF/SUBSPICLK_N_DIFF_30") (pintype "passive"))
    )
    (net (code "58") (name "/RTS_FTDI") (class "Default")
      (node (ref "Q1") (pin "2") (pinfunction "E_2") (pintype "passive"))
      (node (ref "R26") (pin "2") (pinfunction "2_2") (pintype "passive"))
      (node (ref "U2") (pin "19") (pinfunction "~{RTS}_19") (pintype "passive"))
    )
    (net (code "59") (name "/RXD_FTDI") (class "Default")
      (node (ref "R16") (pin "2") (pinfunction "2_2") (pintype "passive"))
      (node (ref "U2") (pin "1") (pinfunction "RXD_1") (pintype "passive"))
    )
    (net (code "60") (name "/TXD_FTDI") (class "Default")
      (node (ref "R18") (pin "2") (pinfunction "2_2") (pintype "passive"))
      (node (ref "U2") (pin "17") (pinfunction "TXD_17") (pintype "passive"))
    )
    (net (code "61") (name "/U0RXD") (class "Default")
      (node (ref "J2") (pin "6") (pinfunction "6_6") (pintype "passive"))
      (node (ref "R18") (pin "1") (pinfunction "1_1") (pintype "passive"))
      (node (ref "U1") (pin "40") (pinfunction "U0RXD/GPIO44/CLK_OUT2_40") (pintype "passive"))
    )
    (net (code "62") (name "/U0TXD") (class "Default")
      (node (ref "J2") (pin "7") (pinfunction "7_7") (pintype "passive"))
      (node (ref "R16") (pin "1") (pinfunction "1_1") (pintype "passive"))
      (node (ref "U1") (pin "39") (pinfunction "U0TXD/GPIO43/CLK_OUT1_39") (pintype "passive"))
    )
    (net (code "63") (name "/VBUS_SENSE") (class "Default")
      (node (ref "R13") (pin "2") (pinfunction "2_2") (pintype "passive"))
      (node (ref "R8") (pin "1") (pinfunction "1_1") (pintype "passive"))
      (node (ref "U2") (pin "16") (pinfunction "CBUS3_16") (pintype "passive"))
    )
    (net (code "64") (name "GND") (class "Default")
      (node (ref "C1") (pin "1") (pinfunction "1_1") (pintype "passive"))
      (node (ref "C10") (pin "1") (pinfunction "1_1") (pintype "passive"))
      (node (ref "C11") (pin "1") (pinfunction "1_1") (pintype "passive"))
      (node (ref "C12") (pin "1") (pinfunction "1_1") (pintype "passive"))
      (node (ref "C13") (pin "1") (pinfunction "1_1") (pintype "passive"))
      (node (ref "C14") (pin "1") (pinfunction "1_1") (pintype "passive"))
      (node (ref "C15") (pin "1") (pinfunction "1_1") (pintype "passive"))
      (node (ref "C16") (pin "1") (pinfunction "1_1") (pintype "passive"))
      (node (ref "C17") (pin "1") (pinfunction "1_1") (pintype "passive"))
      (node (ref "C2") (pin "1") (pinfunction "1_1") (pintype "passive"))
      (node (ref "C3") (pin "1") (pinfunction "1_1") (pintype "passive"))
      (node (ref "C4") (pin "1") (pinfunction "1_1") (pintype "passive"))
      (node (ref "C5") (pin "1") (pinfunction "1_1") (pintype "passive"))
      (node (ref "C6") (pin "1") (pinfunction "1_1") (pintype "passive"))
      (node (ref "C7") (pin "1") (pinfunction "1_1") (pintype "passive"))
      (node (ref "C8") (pin "1") (pinfunction "1_1") (pintype "passive"))
      (node (ref "C9") (pin "1") (pinfunction "1_1") (pintype "passive"))
      (node (ref "D1") (pin "1") (pinfunction "1_1") (pintype "passive"))
      (node (ref "D2") (pin "1") (pinfunction "1_1") (pintype "passive"))
      (node (ref "D3") (pin "2") (pinfunction "2_2") (pintype "passive"))
      (node (ref "D4") (pin "1") (pinfunction "1_1") (pintype "passive"))
      (node (ref "D6") (pin "1") (pinfunction "1_1") (pintype "passive"))
      (node (ref "D7") (pin "1") (pinfunction "1_1") (pintype "passive"))
      (node (ref "D8") (pin "2") (pinfunction "2_2") (pintype "passive"))
      (node (ref "J1") (pin "1") (pinfunction "1_1") (pintype "passive"))
      (node (ref "J1") (pin "23") (pinfunction "23_23") (pintype "passive"))
      (node (ref "J2") (pin "2") (pinfunction "2_2") (pintype "passive"))
      (node (ref "J2") (pin "24") (pinfunction "24_24") (pintype "passive"))
      (node (ref "J3") (pin "A1B12") (pinfunction "GND_A1B12_A1B12") (pintype "passive"))
      (node (ref "J3") (pin "B1A12") (pinfunction "GND_B1_B1A12") (pintype "passive"))
      (node (ref "J3") (pin "S1") (pinfunction "SHIELD_1_S1") (pintype "passive"))
      (node (ref "J3") (pin "S2") (pinfunction "SHIELD_2_S2") (pintype "passive"))
      (node (ref "J3") (pin "S3") (pinfunction "SHIELD_3_S3") (pintype "passive"))
      (node (ref "J3") (pin "S4") (pinfunction "SHIELD_4_S4") (pintype "passive"))
      (node (ref "J4") (pin "A1B12") (pinfunction "GND_A1B12_A1B12") (pintype "passive"))
      (node (ref "J4") (pin "B1A12") (pinfunction "GND_B1_B1A12") (pintype "passive"))
      (node (ref "J4") (pin "S1") (pinfunction "SHIELD_1_S1") (pintype "passive"))
      (node (ref "J4") (pin "S2") (pinfunction "SHIELD_2_S2") (pintype "passive"))
      (node (ref "J4") (pin "S3") (pinfunction "SHIELD_3_S3") (pintype "passive"))
      (node (ref "J4") (pin "S4") (pinfunction "SHIELD_4_S4") (pintype "passive"))
      (node (ref "R10") (pin "1") (pinfunction "1_1") (pintype "passive"))
      (node (ref "R13") (pin "1") (pinfunction "1_1") (pintype "passive"))
      (node (ref "R14") (pin "1") (pinfunction "1_1") (pintype "passive"))
      (node (ref "R15") (pin "1") (pinfunction "1_1") (pintype "passive"))
      (node (ref "R7") (pin "2") (pinfunction "2_2") (pintype "passive"))
      (node (ref "R9") (pin "1") (pinfunction "1_1") (pintype "passive"))
      (node (ref "SW1") (pin "3") (pinfunction "3_3") (pintype "passive"))
      (node (ref "SW1") (pin "4") (pinfunction "4_4") (pintype "passive"))
      (node (ref "SW2") (pin "3") (pinfunction "3_3") (pintype "passive"))
      (node (ref "SW2") (pin "4") (pinfunction "4_4") (pintype "passive"))
      (node (ref "U1") (pin "1") (pinfunction "GND_01_1") (pintype "passive"))
      (node (ref "U1") (pin "2") (pinfunction "GND_02_2") (pintype "passive"))
      (node (ref "U1") (pin "42") (pinfunction "GND_42") (pintype "passive"))
      (node (ref "U1") (pin "43") (pinfunction "GND_43") (pintype "passive"))
      (node (ref "U1") (pin "46") (pinfunction "GND_46_46") (pintype "passive"))
      (node (ref "U1") (pin "47") (pinfunction "GND_47_47") (pintype "passive"))
      (node (ref "U1") (pin "48") (pinfunction "GND_48_48") (pintype "passive"))
      (node (ref "U1") (pin "49") (pinfunction "GND_49_49") (pintype "passive"))
      (node (ref "U1") (pin "50") (pinfunction "GND_50_50") (pintype "passive"))
      (node (ref "U1") (pin "51") (pinfunction "GND_51_51") (pintype "passive"))
      (node (ref "U1") (pin "52") (pinfunction "GND_52_52") (pintype "passive"))
      (node (ref "U1") (pin "53") (pinfunction "GND_53_53") (pintype "passive"))
      (node (ref "U1") (pin "54") (pinfunction "GND_54_54") (pintype "passive"))
      (node (ref "U1") (pin "55") (pinfunction "GND_55_55") (pintype "passive"))
      (node (ref "U1") (pin "56") (pinfunction "GND_56_56") (pintype "passive"))
      (node (ref "U1") (pin "57") (pinfunction "GND_57_57") (pintype "passive"))
      (node (ref "U1") (pin "58") (pinfunction "GND_58_58") (pintype "passive"))
      (node (ref "U1") (pin "59") (pinfunction "GND_59_59") (pintype "passive"))
      (node (ref "U1") (pin "60") (pinfunction "GND_60_60") (pintype "passive"))
      (node (ref "U1") (pin "61") (pinfunction "GND_61_61") (pintype "passive"))
      (node (ref "U1") (pin "62") (pinfunction "GND_62_62") (pintype "passive"))
      (node (ref "U1") (pin "63") (pinfunction "GND_63_63") (pintype "passive"))
      (node (ref "U1") (pin "64") (pinfunction "GND_64_64") (pintype "passive"))
      (node (ref "U1") (pin "65") (pinfunction "GND_65_65") (pintype "passive"))
      (node (ref "U1") (pin "66") (pinfunction "GND_66_66") (pintype "passive"))
      (node (ref "U1") (pin "67") (pinfunction "GND_67_67") (pintype "passive"))
      (node (ref "U1") (pin "68") (pinfunction "GND_68_68") (pintype "passive"))
      (node (ref "U1") (pin "69") (pinfunction "GND_69_69") (pintype "passive"))
      (node (ref "U1") (pin "70") (pinfunction "GND_70_70") (pintype "passive"))
      (node (ref "U1") (pin "71") (pinfunction "GND_71_71") (pintype "passive"))
      (node (ref "U1") (pin "72") (pinfunction "GND_72_72") (pintype "passive"))
      (node (ref "U1") (pin "73") (pinfunction "GND_73_73") (pintype "passive"))
      (node (ref "U2") (pin "13") (pinfunction "GND_13") (pintype "passive"))
      (node (ref "U2") (pin "21") (pinfunction "GND_21") (pintype "passive"))
      (node (ref "U2") (pin "3") (pinfunction "GND_3") (pintype "passive"))
      (node (ref "U3") (pin "2") (pinfunction "GND_2") (pintype "power_in"))
      (node (ref "U3") (pin "4") (pinfunction "GND_4") (pintype "power_in"))
    )
    (net (code "65") (name "Net-(D4-Pad2)") (class "Default")
      (node (ref "D4") (pin "2") (pinfunction "2_2") (pintype "passive"))
      (node (ref "R11") (pin "1") (pinfunction "1_1") (pintype "passive"))
    )
    (net (code "66") (name "Net-(D5-Pad2)") (class "Default")
      (node (ref "D5") (pin "2") (pinfunction "2_2") (pintype "passive"))
      (node (ref "R12") (pin "1") (pinfunction "1_1") (pintype "passive"))
    )
    (net (code "67") (name "Net-(J3-CC2)") (class "Default")
      (node (ref "J3") (pin "B5") (pinfunction "CC2_B5") (pintype "passive"))
      (node (ref "R9") (pin "2") (pinfunction "2_2") (pintype "passive"))
    )
    (net (code "68") (name "Net-(J3-CCS1)") (class "Default")
      (node (ref "J3") (pin "A5") (pinfunction "CCS1_A5") (pintype "passive"))
      (node (ref "R10") (pin "2") (pinfunction "2_2") (pintype "passive"))
    )
    (net (code "69") (name "Net-(J4-CC2)") (class "Default")
      (node (ref "J4") (pin "B5") (pinfunction "CC2_B5") (pintype "passive"))
      (node (ref "R14") (pin "2") (pinfunction "2_2") (pintype "passive"))
    )
    (net (code "70") (name "Net-(J4-CCS1)") (class "Default")
      (node (ref "J4") (pin "A5") (pinfunction "CCS1_A5") (pintype "passive"))
      (node (ref "R15") (pin "2") (pinfunction "2_2") (pintype "passive"))
    )
    (net (code "71") (name "Net-(Q1-B)") (class "Default")
      (node (ref "Q1") (pin "1") (pinfunction "B_1") (pintype "passive"))
      (node (ref "R23") (pin "1") (pinfunction "1_1") (pintype "passive"))
    )
    (net (code "72") (name "Net-(Q2-B)") (class "Default")
      (node (ref "Q2") (pin "1") (pinfunction "B_1") (pintype "passive"))
      (node (ref "R26") (pin "1") (pinfunction "1_1") (pintype "passive"))
    )
    (net (code "73") (name "Net-(U2-CBUS0)") (class "Default")
      (node (ref "R7") (pin "1") (pinfunction "1_1") (pintype "passive"))
      (node (ref "U2") (pin "15") (pinfunction "CBUS0_15") (pintype "passive"))
    )
    (net (code "74") (name "unconnected-(J1-Pad24)") (class "Default")
      (node (ref "J1") (pin "24") (pinfunction "24_24") (pintype "passive+no_connect"))
    )
    (net (code "75") (name "unconnected-(J3-SBU2-PadB8)") (class "Default")
      (node (ref "J3") (pin "B8") (pinfunction "SBU2_B8") (pintype "passive+no_connect"))
    )
    (net (code "76") (name "unconnected-(J3-SUB1-PadA8)") (class "Default")
      (node (ref "J3") (pin "A8") (pinfunction "SUB1_A8") (pintype "passive+no_connect"))
    )
    (net (code "77") (name "unconnected-(J4-SBU2-PadB8)") (class "Default")
      (node (ref "J4") (pin "B8") (pinfunction "SBU2_B8") (pintype "passive+no_connect"))
    )
    (net (code "78") (name "unconnected-(J4-SUB1-PadA8)") (class "Default")
      (node (ref "J4") (pin "A8") (pinfunction "SUB1_A8") (pintype "passive+no_connect"))
    )
    (net (code "79") (name "unconnected-(U2-CBUS1-Pad14)") (class "Default")
      (node (ref "U2") (pin "14") (pinfunction "CBUS1_14") (pintype "passive+no_connect"))
    )
    (net (code "80") (name "unconnected-(U2-CBUS2-Pad7)") (class "Default")
      (node (ref "U2") (pin "7") (pinfunction "CBUS2_7") (pintype "passive+no_connect"))
    )
    (net (code "81") (name "unconnected-(U2-~{CTS}-Pad6)") (class "Default")
      (node (ref "U2") (pin "6") (pinfunction "~{CTS}_6") (pintype "passive+no_connect"))
    )
    (net (code "82") (name "unconnected-(U2-~{DCD}-Pad5)") (class "Default")
      (node (ref "U2") (pin "5") (pinfunction "~{DCD}_5") (pintype "passive+no_connect"))
    )
    (net (code "83") (name "unconnected-(U2-~{DSR}-Pad4)") (class "Default")
      (node (ref "U2") (pin "4") (pinfunction "~{DSR}_4") (pintype "passive+no_connect"))
    )
    (net (code "84") (name "unconnected-(U2-~{RI}-Pad2)") (class "Default")
      (node (ref "U2") (pin "2") (pinfunction "~{RI}_2") (pintype "passive+no_connect"))
    )
  )
)
